# Schematic_proiect_v112.net
KiCad netlist of a schematic drawn in EAGLE
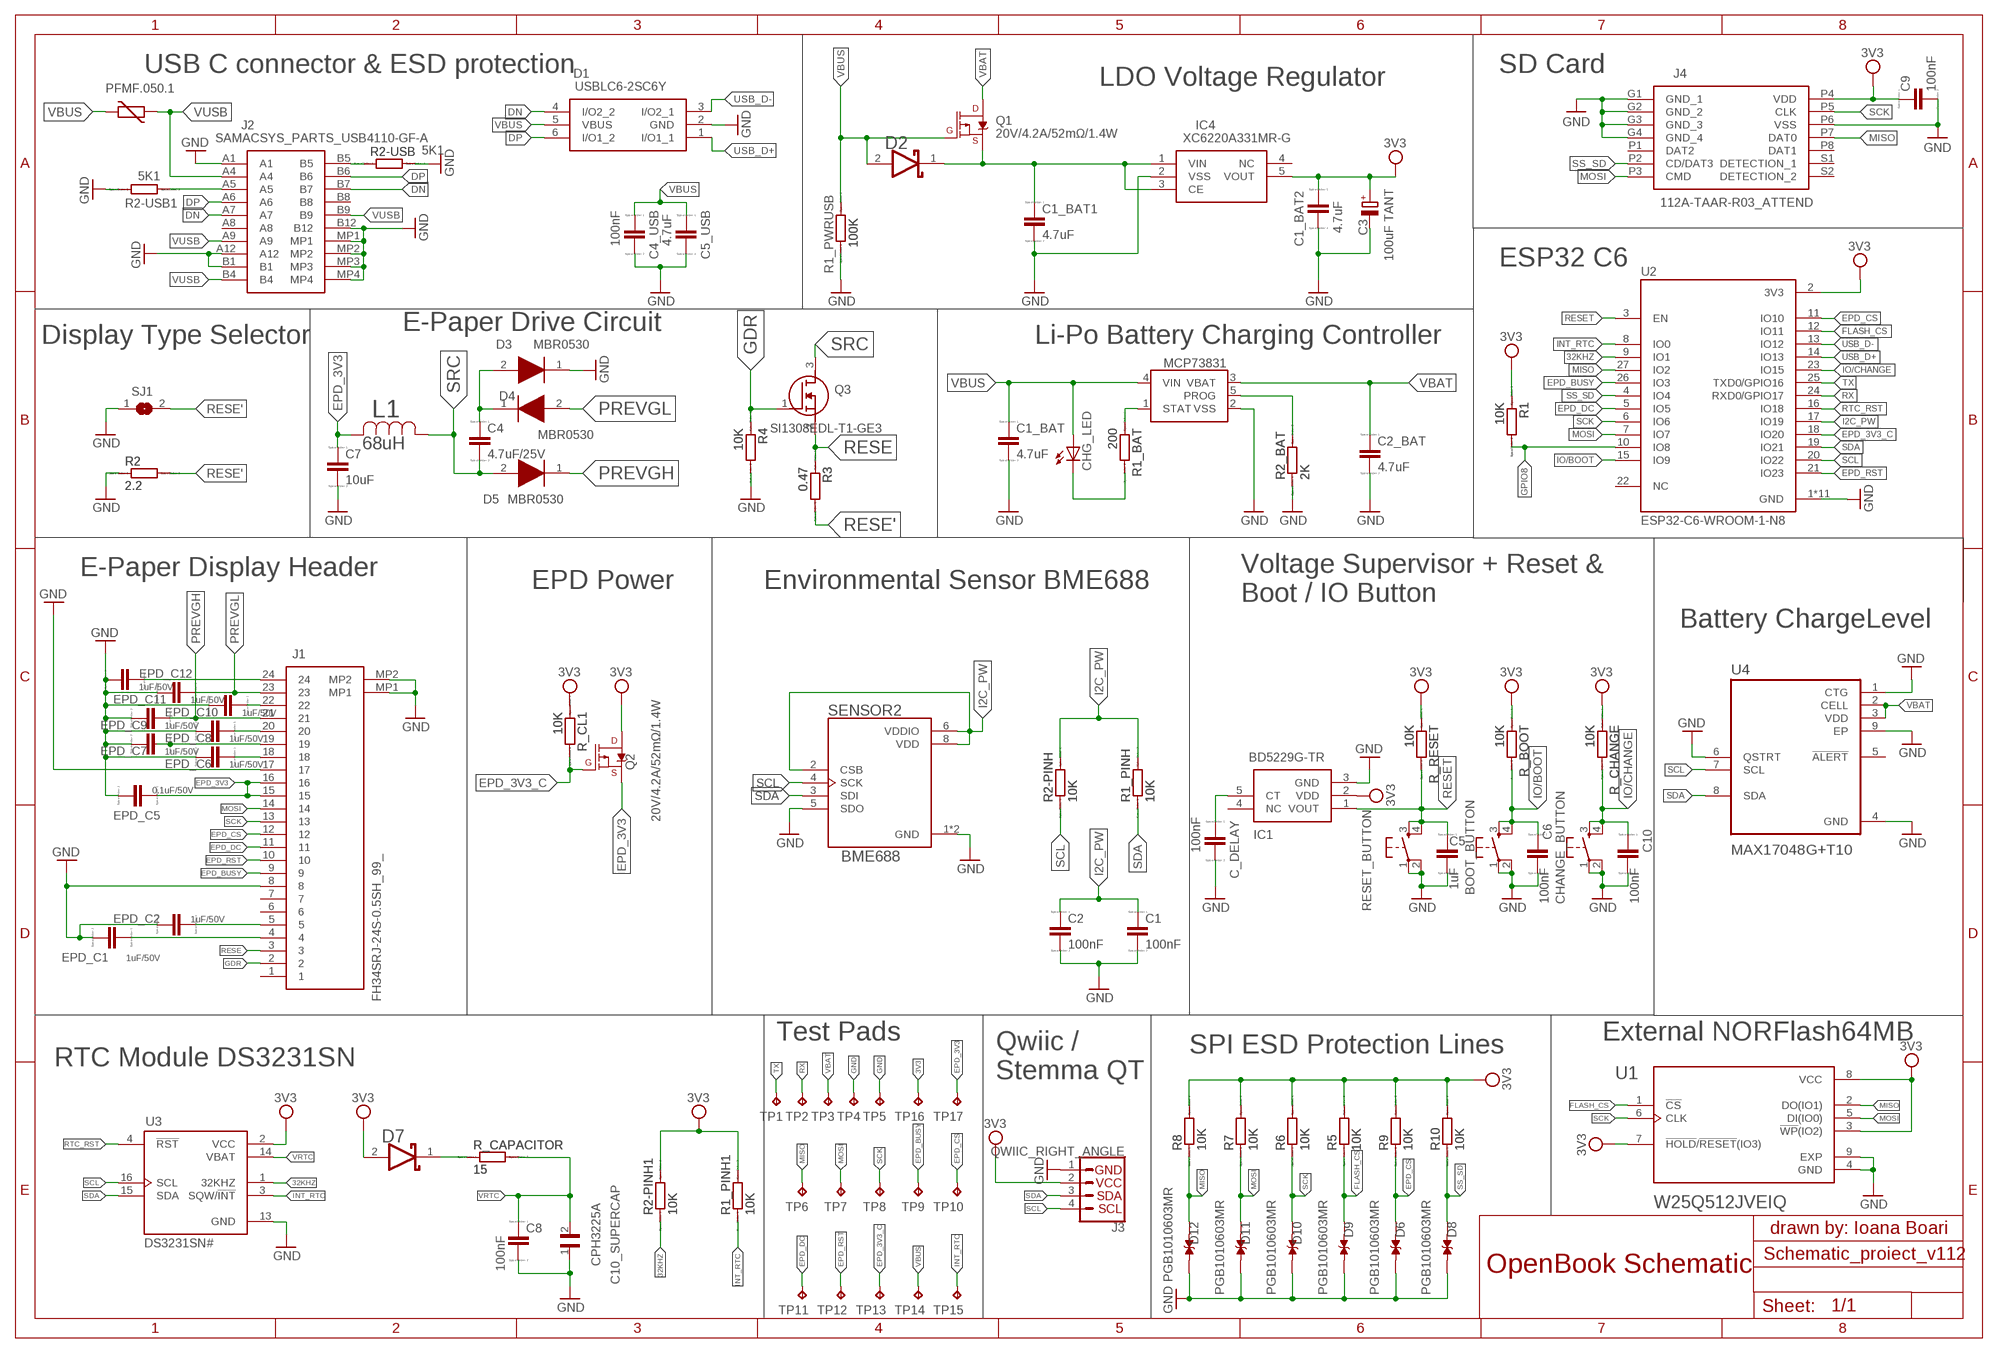
[diagram p0: schematic, sheet 1]

(export (version "E")
  (design (tool "Eeschema 10.0.6"))
  (components
    (comp (ref "BOOT_BUTTON")
      (value "BUTTON_CUSYOMV1")
      (footprint "eagle-import:MYBUTTON")
      (libsource (lib "eagle-import") (part "BUTTON_CUSYOMV1"))
    )
    (comp (ref "C1")
      (value "100nF")
      (footprint "eagle-import:ESP32_WROVER_EAGLE-LTSPICE_C0402")
      (libsource (lib "eagle-import") (part "ESP32_WROVER_EAGLE-LTSPICE_CC0402"))
    )
    (comp (ref "C1_BAT")
      (value "4.7uF")
      (footprint "eagle-import:ESP32_WROVER_EAGLE-LTSPICE_C0402")
      (libsource (lib "eagle-import") (part "ESP32_WROVER_EAGLE-LTSPICE_CC0402"))
    )
    (comp (ref "C1_BAT1")
      (value "4.7uF")
      (footprint "eagle-import:ESP32_WROVER_EAGLE-LTSPICE_C0402")
      (libsource (lib "eagle-import") (part "ESP32_WROVER_EAGLE-LTSPICE_CC0402"))
    )
    (comp (ref "C1_BAT2")
      (value "4.7uF")
      (footprint "eagle-import:EAGLE-LTSPICE_C0402")
      (libsource (lib "eagle-import") (part "EAGLE-LTSPICE_CC0402"))
    )
    (comp (ref "C2")
      (value "100nF")
      (footprint "eagle-import:ESP32_WROVER_EAGLE-LTSPICE_C0402")
      (libsource (lib "eagle-import") (part "ESP32_WROVER_EAGLE-LTSPICE_CC0402"))
    )
    (comp (ref "C2_BAT")
      (value "4.7uF")
      (footprint "eagle-import:ESP32_WROVER_EAGLE-LTSPICE_C0402")
      (libsource (lib "eagle-import") (part "ESP32_WROVER_EAGLE-LTSPICE_CC0402"))
    )
    (comp (ref "C3")
      (value "100uF TANT")
      (footprint "eagle-import:RCL_CT3528")
      (libsource (lib "eagle-import") (part "RCL_CPOL-EUCT3528"))
    )
    (comp (ref "C4")
      (value "4.7uF/25V")
      (footprint "eagle-import:ESP32_WROVER_EAGLE-LTSPICE_C0402")
      (libsource (lib "eagle-import") (part "ESP32_WROVER_EAGLE-LTSPICE_CC0402"))
    )
    (comp (ref "C4_USB")
      (value "100nF")
      (footprint "eagle-import:ESP32_WROVER_EAGLE-LTSPICE_C0402")
      (libsource (lib "eagle-import") (part "ESP32_WROVER_EAGLE-LTSPICE_CC0402"))
    )
    (comp (ref "C5")
      (value "1uF")
      (footprint "eagle-import:ESP32_WROVER_EAGLE-LTSPICE_C0402")
      (libsource (lib "eagle-import") (part "ESP32_WROVER_EAGLE-LTSPICE_CC0402"))
    )
    (comp (ref "C5_USB")
      (value "4.7uF")
      (footprint "eagle-import:ESP32_WROVER_EAGLE-LTSPICE_C0402")
      (libsource (lib "eagle-import") (part "ESP32_WROVER_EAGLE-LTSPICE_CC0402"))
    )
    (comp (ref "C6")
      (value "100nF")
      (footprint "eagle-import:ESP32_WROVER_EAGLE-LTSPICE_C0402")
      (libsource (lib "eagle-import") (part "ESP32_WROVER_EAGLE-LTSPICE_CC0402"))
    )
    (comp (ref "C7")
      (value "10uF")
      (footprint "eagle-import:ESP32_WROVER_EAGLE-LTSPICE_C0402")
      (libsource (lib "eagle-import") (part "ESP32_WROVER_EAGLE-LTSPICE_CC0402"))
    )
    (comp (ref "C8")
      (value "100nF")
      (footprint "eagle-import:ESP32_WROVER_EAGLE-LTSPICE_C0402")
      (libsource (lib "eagle-import") (part "ESP32_WROVER_EAGLE-LTSPICE_CC0402"))
    )
    (comp (ref "C9")
      (value "100nF")
      (footprint "eagle-import:ESP32_WROVER_EAGLE-LTSPICE_C0402")
      (libsource (lib "eagle-import") (part "ESP32_WROVER_EAGLE-LTSPICE_CC0402"))
    )
    (comp (ref "C10")
      (value "100nF")
      (footprint "eagle-import:ESP32_WROVER_EAGLE-LTSPICE_C0402")
      (libsource (lib "eagle-import") (part "ESP32_WROVER_EAGLE-LTSPICE_CC0402"))
    )
    (comp (ref "C10_SUPERCAP")
      (value "CPH3225A")
      (footprint "eagle-import:CAPCP3225X100N")
      (fields (field (name "MF") "Seiko Instruments"))
      (libsource (lib "eagle-import") (part "CPH3225A"))
    )
    (comp (ref "CHANGE_BUTTON")
      (value "BUTTON_CUSYOMV1")
      (footprint "eagle-import:MYBUTTON")
      (libsource (lib "eagle-import") (part "BUTTON_CUSYOMV1"))
    )
    (comp (ref "CHG_LED")
      (value "ADAFRUIT_LEDCHIP-LED0603")
      (footprint "eagle-import:ADAFRUIT_CHIP-LED0603")
      (libsource (lib "eagle-import") (part "ADAFRUIT_LEDCHIP-LED0603"))
    )
    (comp (ref "C_DELAY")
      (value "100nF")
      (footprint "eagle-import:ESP32_WROVER_EAGLE-LTSPICE_C0402")
      (libsource (lib "eagle-import") (part "ESP32_WROVER_EAGLE-LTSPICE_CC0402"))
    )
    (comp (ref "D1")
      (value "USBLC6-2SC6Y")
      (footprint "eagle-import:SOT95P280X145-6N")
      (fields (field (name "MF") "STMicroelectronics"))
      (libsource (lib "eagle-import") (part "USBLC6-2SC6Y"))
    )
    (comp (ref "D2")
      (value "ESP32_WROVER_AVX---SD0805S020S1R0_AVX_SD0805S020S1R0_0_0AVX_SD0805S020S1R0_0_0")
      (footprint "eagle-import:ESP32_WROVER_AVX---SD0805S020S1R0_AVX_SD0805S020S1R0_0")
      (fields
        (field (name "DIGIKEY_PART_NUMBER") "478-7800-1-ND")
        (field (name "MF") "AVX")
        (field (name "MOUSER_PART_NUMBER") "581-SD0805S020S1R0")
      )
      (libsource (lib "eagle-import") (part "ESP32_WROVER_AVX---SD0805S020S1R0_AVX_SD0805S020S1R0_0_0AVX_SD0805S020S1R0_0_0"))
    )
    (comp (ref "D3")
      (value "MBR0530")
      (footprint "eagle-import:SOD3716X135N")
      (fields (field (name "MF") "ON Semiconductor"))
      (libsource (lib "eagle-import") (part "MBR0530"))
    )
    (comp (ref "D4")
      (value "MBR0530")
      (footprint "eagle-import:SOD3716X135N")
      (fields (field (name "MF") "ON Semiconductor"))
      (libsource (lib "eagle-import") (part "MBR0530"))
    )
    (comp (ref "D5")
      (value "MBR0530")
      (footprint "eagle-import:SOD3716X135N")
      (fields (field (name "MF") "ON Semiconductor"))
      (libsource (lib "eagle-import") (part "MBR0530"))
    )
    (comp (ref "D6")
      (value "PGB1010603MR")
      (footprint "eagle-import:DIOC1608X36N")
      (fields (field (name "MF") "Littelfuse Inc."))
      (libsource (lib "eagle-import") (part "PGB1010603MR"))
    )
    (comp (ref "D7")
      (value "ESP32_WROVER_AVX---SD0805S020S1R0_AVX_SD0805S020S1R0_0_0AVX_SD0805S020S1R0_0_0")
      (footprint "eagle-import:ESP32_WROVER_AVX---SD0805S020S1R0_AVX_SD0805S020S1R0_0")
      (fields
        (field (name "DIGIKEY_PART_NUMBER") "478-7800-1-ND")
        (field (name "MF") "AVX")
        (field (name "MOUSER_PART_NUMBER") "581-SD0805S020S1R0")
      )
      (libsource (lib "eagle-import") (part "ESP32_WROVER_AVX---SD0805S020S1R0_AVX_SD0805S020S1R0_0_0AVX_SD0805S020S1R0_0_0"))
    )
    (comp (ref "D8")
      (value "PGB1010603MR")
      (footprint "eagle-import:DIOC1608X36N")
      (fields (field (name "MF") "Littelfuse Inc."))
      (libsource (lib "eagle-import") (part "PGB1010603MR"))
    )
    (comp (ref "D9")
      (value "PGB1010603MR")
      (footprint "eagle-import:DIOC1608X36N")
      (fields (field (name "MF") "Littelfuse Inc."))
      (libsource (lib "eagle-import") (part "PGB1010603MR"))
    )
    (comp (ref "D10")
      (value "PGB1010603MR")
      (footprint "eagle-import:DIOC1608X36N")
      (fields (field (name "MF") "Littelfuse Inc."))
      (libsource (lib "eagle-import") (part "PGB1010603MR"))
    )
    (comp (ref "D11")
      (value "PGB1010603MR")
      (footprint "eagle-import:DIOC1608X36N")
      (fields (field (name "MF") "Littelfuse Inc."))
      (libsource (lib "eagle-import") (part "PGB1010603MR"))
    )
    (comp (ref "D12")
      (value "PGB1010603MR")
      (footprint "eagle-import:DIOC1608X36N")
      (fields (field (name "MF") "Littelfuse Inc."))
      (libsource (lib "eagle-import") (part "PGB1010603MR"))
    )
    (comp (ref "EPD_C1")
      (value "1uF/50V")
      (footprint "eagle-import:ESP32_WROVER_EAGLE-LTSPICE_C0402")
      (libsource (lib "eagle-import") (part "ESP32_WROVER_EAGLE-LTSPICE_CC0402"))
    )
    (comp (ref "EPD_C2")
      (value "1uF/50V")
      (footprint "eagle-import:ESP32_WROVER_EAGLE-LTSPICE_C0402")
      (libsource (lib "eagle-import") (part "ESP32_WROVER_EAGLE-LTSPICE_CC0402"))
    )
    (comp (ref "EPD_C5")
      (value "0.1uF/50V")
      (footprint "eagle-import:ESP32_WROVER_EAGLE-LTSPICE_C0402")
      (libsource (lib "eagle-import") (part "ESP32_WROVER_EAGLE-LTSPICE_CC0402"))
    )
    (comp (ref "EPD_C6")
      (value "1uF/50V")
      (footprint "eagle-import:ESP32_WROVER_EAGLE-LTSPICE_C0402")
      (libsource (lib "eagle-import") (part "ESP32_WROVER_EAGLE-LTSPICE_CC0402"))
    )
    (comp (ref "EPD_C7")
      (value "1uF/50V")
      (footprint "eagle-import:ESP32_WROVER_EAGLE-LTSPICE_C0402")
      (libsource (lib "eagle-import") (part "ESP32_WROVER_EAGLE-LTSPICE_CC0402"))
    )
    (comp (ref "EPD_C8")
      (value "1uF/50V")
      (footprint "eagle-import:ESP32_WROVER_EAGLE-LTSPICE_C0402")
      (libsource (lib "eagle-import") (part "ESP32_WROVER_EAGLE-LTSPICE_CC0402"))
    )
    (comp (ref "EPD_C9")
      (value "1uF/50V")
      (footprint "eagle-import:ESP32_WROVER_EAGLE-LTSPICE_C0402")
      (libsource (lib "eagle-import") (part "ESP32_WROVER_EAGLE-LTSPICE_CC0402"))
    )
    (comp (ref "EPD_C10")
      (value "1uF/50V")
      (footprint "eagle-import:ESP32_WROVER_EAGLE-LTSPICE_C0402")
      (libsource (lib "eagle-import") (part "ESP32_WROVER_EAGLE-LTSPICE_CC0402"))
    )
    (comp (ref "EPD_C11")
      (value "1uF/50V")
      (footprint "eagle-import:ESP32_WROVER_EAGLE-LTSPICE_C0402")
      (libsource (lib "eagle-import") (part "ESP32_WROVER_EAGLE-LTSPICE_CC0402"))
    )
    (comp (ref "EPD_C12")
      (value "1uF/50V")
      (footprint "eagle-import:ESP32_WROVER_EAGLE-LTSPICE_C0402")
      (libsource (lib "eagle-import") (part "ESP32_WROVER_EAGLE-LTSPICE_CC0402"))
    )
    (comp (ref "IC1")
      (value "BD5229G-TR")
      (footprint "eagle-import:SOT95P280X125-5N")
      (fields (field (name "MOUSER_PART_NUMBER") "755-BD5229G-TR"))
      (libsource (lib "eagle-import") (part "BD5229G-TR"))
    )
    (comp (ref "IC4")
      (value "XC6220A331MR-G")
      (footprint "eagle-import:SOT95P280X120-5N")
      (fields (field (name "MOUSER_PART_NUMBER") "865-XC6220A331MR-G"))
      (libsource (lib "eagle-import") (part "XC6220A331MR-G"))
    )
    (comp (ref "J1")
      (value "FH34SRJ-24S-0.5SH_99_")
      (footprint "eagle-import:FH34SRJ24S05SH99")
      (fields
        (field (name "MANUFACTURER_PART_NUMBER") "FH34SRJ-24S-0.5SH(99)")
        (field (name "MOUSER_PART_NUMBER") "798-FH34SRJ24S05SH99")
      )
      (libsource (lib "eagle-import") (part "FH34SRJ-24S-0.5SH_99_"))
    )
    (comp (ref "J2")
      (value "SAMACSYS_PARTS_USB4110-GF-A")
      (footprint "eagle-import:SAMACSYS_PARTS_USB4110GFA")
      (fields
        (field (name "MANUFACTURER_PART_NUMBER") "USB4110-GF-A")
        (field (name "MOUSER_PART_NUMBER") "640-USB4110-GF-A")
      )
      (libsource (lib "eagle-import") (part "SAMACSYS_PARTS_USB4110-GF-A"))
    )
    (comp (ref "J3")
      (value "QWIIC_RIGHT_ANGLE")
      (footprint "eagle-import:JST04_1MM_RA")
      (libsource (lib "eagle-import") (part "QWIIC_CONNECTORJS-1MM"))
    )
    (comp (ref "J4")
      (value "112A-TAAR-R03_ATTEND")
      (footprint "eagle-import:112ATAARR03ATTEND")
      (fields (field (name "MANUFACTURER_PART_NUMBER") "112A-TAAR-R03 ATTEND"))
      (libsource (lib "eagle-import") (part "112A-TAAR-R03_ATTEND"))
    )
    (comp (ref "L1")
      (value "68uH")
      (footprint "eagle-import:IND_4828-WE-TPC_WRE")
      (fields
        (field (name "MANUFACTURER_PART_NUMBER") "744043680")
        (field (name "COPYRIGHT") "Copyright (C) 2024 Ultra Librarian. All rights reserved.")
      )
      (libsource (lib "eagle-import") (part "744043680IND_4828-WE-TPC_WRE"))
    )
    (comp (ref "MCP73831")
      (value "MCP73831")
      (footprint "eagle-import:ESP32_WROVER_SPARKFUN-IC-POWER_SOT23-5")
      (libsource (lib "eagle-import") (part "ESP32_WROVER_SPARKFUN-IC-POWER_MCP73831"))
    )
    (comp (ref "PFMF.050.1")
      (value "ESP32C6_VARISTORCN1812")
      (footprint "eagle-import:ESP32C6_VARISTOR_CT_CN1812")
      (libsource (lib "eagle-import") (part "ESP32C6_VARISTORCN1812"))
    )
    (comp (ref "Q1")
      (value "20V/4.2A/52mΩ/1.4W")
      (footprint "eagle-import:ESP32_WROVER_SPARKFUN-DISCRETESEMI_SOT23-3")
      (libsource (lib "eagle-import") (part "ESP32_WROVER_SPARKFUN-DISCRETESEMI_MOSFET_PCH-DMG2305UX-7"))
    )
    (comp (ref "Q2")
      (value "20V/4.2A/52mΩ/1.4W")
      (footprint "eagle-import:ESP32_WROVER_SPARKFUN-DISCRETESEMI_SOT23-3")
      (libsource (lib "eagle-import") (part "ESP32_WROVER_SPARKFUN-DISCRETESEMI_MOSFET_PCH-DMG2305UX-7"))
    )
    (comp (ref "Q3")
      (value "SI1308EDL-T1-GE3")
      (footprint "eagle-import:SOT65P210X110-3N")
      (fields (field (name "MF") "Vishay Siliconix"))
      (libsource (lib "eagle-import") (part "SI1308EDL-T1-GE3"))
    )
    (comp (ref "R1")
      (value "10K")
      (footprint "eagle-import:ESP32_WROVER_EAGLE-LTSPICE_R0402")
      (libsource (lib "eagle-import") (part "ESP32_WROVER_EAGLE-LTSPICE_RR0402"))
    )
    (comp (ref "R1_BAT")
      (value "200")
      (footprint "eagle-import:ESP32_WROVER_EAGLE-LTSPICE_R0402")
      (libsource (lib "eagle-import") (part "ESP32_WROVER_EAGLE-LTSPICE_RR0402"))
    )
    (comp (ref "R1_PINH")
      (value "10K")
      (footprint "eagle-import:ESP32_WROVER_EAGLE-LTSPICE_R0402")
      (libsource (lib "eagle-import") (part "ESP32_WROVER_EAGLE-LTSPICE_RR0402"))
    )
    (comp (ref "R1_PINH1")
      (value "10K")
      (footprint "eagle-import:ESP32_WROVER_EAGLE-LTSPICE_R0402")
      (libsource (lib "eagle-import") (part "ESP32_WROVER_EAGLE-LTSPICE_RR0402"))
    )
    (comp (ref "R1_PWRUSB")
      (value "100K")
      (footprint "eagle-import:ESP32_WROVER_EAGLE-LTSPICE_R0402")
      (libsource (lib "eagle-import") (part "ESP32_WROVER_EAGLE-LTSPICE_RR0402"))
    )
    (comp (ref "R2")
      (value "2.2")
      (footprint "eagle-import:ESP32_WROVER_EAGLE-LTSPICE_R0402")
      (libsource (lib "eagle-import") (part "ESP32_WROVER_EAGLE-LTSPICE_RR0402"))
    )
    (comp (ref "R2-PINH")
      (value "10K")
      (footprint "eagle-import:ESP32_WROVER_EAGLE-LTSPICE_R0402")
      (libsource (lib "eagle-import") (part "ESP32_WROVER_EAGLE-LTSPICE_RR0402"))
    )
    (comp (ref "R2-PINH1")
      (value "10K")
      (footprint "eagle-import:ESP32_WROVER_EAGLE-LTSPICE_R0402")
      (libsource (lib "eagle-import") (part "ESP32_WROVER_EAGLE-LTSPICE_RR0402"))
    )
    (comp (ref "R2-USB")
      (value "5K1")
      (footprint "eagle-import:ESP32_WROVER_EAGLE-LTSPICE_R0402")
      (libsource (lib "eagle-import") (part "ESP32_WROVER_EAGLE-LTSPICE_RR0402"))
    )
    (comp (ref "R2-USB1")
      (value "5K1")
      (footprint "eagle-import:ESP32_WROVER_EAGLE-LTSPICE_R0402")
      (libsource (lib "eagle-import") (part "ESP32_WROVER_EAGLE-LTSPICE_RR0402"))
    )
    (comp (ref "R2_BAT")
      (value "2K")
      (footprint "eagle-import:ESP32_WROVER_EAGLE-LTSPICE_R0402")
      (libsource (lib "eagle-import") (part "ESP32_WROVER_EAGLE-LTSPICE_RR0402"))
    )
    (comp (ref "R3")
      (value "0.47")
      (footprint "eagle-import:ESP32_WROVER_EAGLE-LTSPICE_R0402")
      (libsource (lib "eagle-import") (part "ESP32_WROVER_EAGLE-LTSPICE_RR0402"))
    )
    (comp (ref "R4")
      (value "10K")
      (footprint "eagle-import:ESP32_WROVER_EAGLE-LTSPICE_R0402")
      (libsource (lib "eagle-import") (part "ESP32_WROVER_EAGLE-LTSPICE_RR0402"))
    )
    (comp (ref "R5")
      (value "10K")
      (footprint "eagle-import:ESP32_WROVER_EAGLE-LTSPICE_R0402")
      (libsource (lib "eagle-import") (part "ESP32_WROVER_EAGLE-LTSPICE_RR0402"))
    )
    (comp (ref "R6")
      (value "10K")
      (footprint "eagle-import:ESP32_WROVER_EAGLE-LTSPICE_R0402")
      (libsource (lib "eagle-import") (part "ESP32_WROVER_EAGLE-LTSPICE_RR0402"))
    )
    (comp (ref "R7")
      (value "10K")
      (footprint "eagle-import:ESP32_WROVER_EAGLE-LTSPICE_R0402")
      (libsource (lib "eagle-import") (part "ESP32_WROVER_EAGLE-LTSPICE_RR0402"))
    )
    (comp (ref "R8")
      (value "10K")
      (footprint "eagle-import:ESP32_WROVER_EAGLE-LTSPICE_R0402")
      (libsource (lib "eagle-import") (part "ESP32_WROVER_EAGLE-LTSPICE_RR0402"))
    )
    (comp (ref "R9")
      (value "10K")
      (footprint "eagle-import:ESP32_WROVER_EAGLE-LTSPICE_R0402")
      (libsource (lib "eagle-import") (part "ESP32_WROVER_EAGLE-LTSPICE_RR0402"))
    )
    (comp (ref "R10")
      (value "10K")
      (footprint "eagle-import:ESP32_WROVER_EAGLE-LTSPICE_R0402")
      (libsource (lib "eagle-import") (part "ESP32_WROVER_EAGLE-LTSPICE_RR0402"))
    )
    (comp (ref "RESET_BUTTON")
      (value "BUTTON_CUSYOMV1")
      (footprint "eagle-import:MYBUTTON")
      (libsource (lib "eagle-import") (part "BUTTON_CUSYOMV1"))
    )
    (comp (ref "R_BOOT")
      (value "10K")
      (footprint "eagle-import:ESP32_WROVER_EAGLE-LTSPICE_R0402")
      (libsource (lib "eagle-import") (part "ESP32_WROVER_EAGLE-LTSPICE_RR0402"))
    )
    (comp (ref "R_CAPACITOR")
      (value "15")
      (footprint "eagle-import:ESP32_WROVER_EAGLE-LTSPICE_R0402")
      (libsource (lib "eagle-import") (part "ESP32_WROVER_EAGLE-LTSPICE_RR0402"))
    )
    (comp (ref "R_CHANGE")
      (value "10K")
      (footprint "eagle-import:ESP32_WROVER_EAGLE-LTSPICE_R0402")
      (libsource (lib "eagle-import") (part "ESP32_WROVER_EAGLE-LTSPICE_RR0402"))
    )
    (comp (ref "R_CL1")
      (value "10K")
      (footprint "eagle-import:ESP32_WROVER_EAGLE-LTSPICE_R0402")
      (libsource (lib "eagle-import") (part "ESP32_WROVER_EAGLE-LTSPICE_RR0402"))
    )
    (comp (ref "R_RESET")
      (value "10K")
      (footprint "eagle-import:ESP32_WROVER_EAGLE-LTSPICE_R0402")
      (libsource (lib "eagle-import") (part "ESP32_WROVER_EAGLE-LTSPICE_RR0402"))
    )
    (comp (ref "SENSOR2")
      (value "BME688")
      (footprint "eagle-import:ESP32_WROVER_BME680_PSON80P300X300X100-8N")
      (fields (field (name "MF") "Bosch Sensortec") (field (name "MP") "BME680"))
      (libsource (lib "eagle-import") (part "ESP32_WROVER_BME680_BME680"))
    )
    (comp (ref "SJ1") (value "SJ") (footprint "eagle-import:SJ") (libsource (lib "eagle-import") (part "SJ")))
    (comp (ref "TP1")
      (value "TPTP20R")
      (footprint "eagle-import:TP20R")
      (libsource (lib "eagle-import") (part "TPTP20R"))
    )
    (comp (ref "TP2")
      (value "TPTP20R")
      (footprint "eagle-import:TP20R")
      (libsource (lib "eagle-import") (part "TPTP20R"))
    )
    (comp (ref "TP3")
      (value "TPTP20R")
      (footprint "eagle-import:TP20R")
      (libsource (lib "eagle-import") (part "TPTP20R"))
    )
    (comp (ref "TP4")
      (value "TPTP20R")
      (footprint "eagle-import:TP20R")
      (libsource (lib "eagle-import") (part "TPTP20R"))
    )
    (comp (ref "TP5")
      (value "TPTP20R")
      (footprint "eagle-import:TP20R")
      (libsource (lib "eagle-import") (part "TPTP20R"))
    )
    (comp (ref "TP6")
      (value "TPTP20R")
      (footprint "eagle-import:TP20R")
      (libsource (lib "eagle-import") (part "TPTP20R"))
    )
    (comp (ref "TP7")
      (value "TPTP20R")
      (footprint "eagle-import:TP20R")
      (libsource (lib "eagle-import") (part "TPTP20R"))
    )
    (comp (ref "TP8")
      (value "TPTP20R")
      (footprint "eagle-import:TP20R")
      (libsource (lib "eagle-import") (part "TPTP20R"))
    )
    (comp (ref "TP9")
      (value "TPTP20R")
      (footprint "eagle-import:TP20R")
      (libsource (lib "eagle-import") (part "TPTP20R"))
    )
    (comp (ref "TP10")
      (value "TPTP20R")
      (footprint "eagle-import:TP20R")
      (libsource (lib "eagle-import") (part "TPTP20R"))
    )
    (comp (ref "TP11")
      (value "TPTP20R")
      (footprint "eagle-import:TP20R")
      (libsource (lib "eagle-import") (part "TPTP20R"))
    )
    (comp (ref "TP12")
      (value "TPTP20R")
      (footprint "eagle-import:TP20R")
      (libsource (lib "eagle-import") (part "TPTP20R"))
    )
    (comp (ref "TP13")
      (value "TPTP20R")
      (footprint "eagle-import:TP20R")
      (libsource (lib "eagle-import") (part "TPTP20R"))
    )
    (comp (ref "TP14")
      (value "TPTP20R")
      (footprint "eagle-import:TP20R")
      (libsource (lib "eagle-import") (part "TPTP20R"))
    )
    (comp (ref "TP15")
      (value "TPTP20R")
      (footprint "eagle-import:TP20R")
      (libsource (lib "eagle-import") (part "TPTP20R"))
    )
    (comp (ref "TP16")
      (value "TPTP20R")
      (footprint "eagle-import:TP20R")
      (libsource (lib "eagle-import") (part "TPTP20R"))
    )
    (comp (ref "TP17")
      (value "TPTP20R")
      (footprint "eagle-import:TP20R")
      (libsource (lib "eagle-import") (part "TPTP20R"))
    )
    (comp (ref "U1")
      (value "W25Q512JVEIQ")
      (footprint "eagle-import:SON127P600X800X80-9N")
      (fields (field (name "MF") "Winbond Electronics"))
      (libsource (lib "eagle-import") (part "W25Q512JVEIQ"))
    )
    (comp (ref "U2")
      (value "ESP32-C6-WROOM-1-N8")
      (footprint "eagle-import:XCVR_ESP32-C6-WROOM-1-N8")
      (fields (field (name "MF") "Espressif Systems"))
      (libsource (lib "eagle-import") (part "ESP32-C6-WROOM-1-N8"))
    )
    (comp (ref "U3")
      (value "DS3231SN#")
      (footprint "eagle-import:SOIC127P1032X265-16N")
      (fields (field (name "MF") "Analog Devices"))
      (libsource (lib "eagle-import") (part "DS3231SN#"))
    )
    (comp (ref "U4")
      (value "MAX17048G+T10")
      (footprint "eagle-import:SON50P200X200X80-9N")
      (fields (field (name "MF") "Analog Devices"))
      (libsource (lib "eagle-import") (part "MAX17048G+T10"))
    )
  )
  (nets
    (net (code "1") (name "3V3") (class "Default")
      (node (ref "C1_BAT2") (pin "1") (pinfunction "1_1") (pintype "passive"))
      (node (ref "C3") (pin "+") (pinfunction "+_+") (pintype "passive"))
      (node (ref "C9") (pin "1") (pinfunction "1_1") (pintype "passive"))
      (node (ref "D7") (pin "2") (pinfunction "ANODE_2") (pintype "bidirectional"))
      (node (ref "IC1") (pin "2") (pinfunction "VDD_2") (pintype "bidirectional"))
      (node (ref "IC4") (pin "5") (pinfunction "VOUT_5") (pintype "bidirectional"))
      (node (ref "J3") (pin "2") (pinfunction "2_2") (pintype "power_in"))
      (node (ref "J4") (pin "P4") (pinfunction "VDD_P4") (pintype "bidirectional"))
      (node (ref "Q2") (pin "3") (pinfunction "D_3") (pintype "bidirectional"))
      (node (ref "R1") (pin "1") (pinfunction "1_1") (pintype "passive"))
      (node (ref "R10") (pin "2") (pinfunction "2_2") (pintype "passive"))
      (node (ref "R1_PINH1") (pin "2") (pinfunction "2_2") (pintype "passive"))
      (node (ref "R2-PINH1") (pin "2") (pinfunction "2_2") (pintype "passive"))
      (node (ref "R5") (pin "2") (pinfunction "2_2") (pintype "passive"))
      (node (ref "R6") (pin "2") (pinfunction "2_2") (pintype "passive"))
      (node (ref "R7") (pin "2") (pinfunction "2_2") (pintype "passive"))
      (node (ref "R8") (pin "2") (pinfunction "2_2") (pintype "passive"))
      (node (ref "R9") (pin "2") (pinfunction "2_2") (pintype "passive"))
      (node (ref "R_BOOT") (pin "1") (pinfunction "1_1") (pintype "passive"))
      (node (ref "R_CHANGE") (pin "1") (pinfunction "1_1") (pintype "passive"))
      (node (ref "R_CL1") (pin "1") (pinfunction "1_1") (pintype "passive"))
      (node (ref "R_RESET") (pin "1") (pinfunction "1_1") (pintype "passive"))
      (node (ref "TP16") (pin "TP") (pinfunction "TP_TP") (pintype "input"))
      (node (ref "U1") (pin "3") (pinfunction "~{WP}(IO2)_3") (pintype "bidirectional"))
      (node (ref "U1") (pin "7") (pinfunction "~{HOLD}/~{RESET}(IO3)_7") (pintype "bidirectional"))
      (node (ref "U1") (pin "8") (pinfunction "VCC_8") (pintype "power_in"))
      (node (ref "U2") (pin "2") (pinfunction "3V3_2") (pintype "power_in"))
      (node (ref "U3") (pin "2") (pinfunction "VCC_2") (pintype "power_in"))
    )
    (net (code "2") (name "32KHZ") (class "Default")
      (node (ref "R2-PINH1") (pin "1") (pinfunction "1_1") (pintype "passive"))
      (node (ref "U2") (pin "9") (pinfunction "IO1_9") (pintype "bidirectional"))
      (node (ref "U3") (pin "1") (pinfunction "32KHZ_1") (pintype "output"))
    )
    (net (code "3") (name "DN") (class "Default")
      (node (ref "D1") (pin "4") (pinfunction "I/O2_2_4") (pintype "bidirectional"))
      (node (ref "J2") (pin "A7") (pinfunction "A7_A7") (pintype "bidirectional"))
      (node (ref "J2") (pin "B7") (pinfunction "B7_B7") (pintype "bidirectional"))
    )
    (net (code "4") (name "DP") (class "Default")
      (node (ref "D1") (pin "6") (pinfunction "I/O1_2_6") (pintype "bidirectional"))
      (node (ref "J2") (pin "A6") (pinfunction "A6_A6") (pintype "bidirectional"))
      (node (ref "J2") (pin "B6") (pinfunction "B6_B6") (pintype "bidirectional"))
    )
    (net (code "5") (name "EPD_3V3") (class "Default")
      (node (ref "C7") (pin "1") (pinfunction "1_1") (pintype "passive"))
      (node (ref "EPD_C5") (pin "1") (pinfunction "1_1") (pintype "passive"))
      (node (ref "J1") (pin "15") (pinfunction "15_15") (pintype "bidirectional"))
      (node (ref "J1") (pin "16") (pinfunction "16_16") (pintype "bidirectional"))
      (node (ref "L1") (pin "2") (pinfunction "2_2") (pintype "passive"))
      (node (ref "Q2") (pin "2") (pinfunction "S_2") (pintype "bidirectional"))
      (node (ref "TP17") (pin "TP") (pinfunction "TP_TP") (pintype "input"))
    )
    (net (code "6") (name "EPD_3V3_C") (class "Default")
      (node (ref "Q2") (pin "1") (pinfunction "G_1") (pintype "bidirectional"))
      (node (ref "R_CL1") (pin "2") (pinfunction "2_2") (pintype "passive"))
      (node (ref "TP13") (pin "TP") (pinfunction "TP_TP") (pintype "input"))
      (node (ref "U2") (pin "18") (pinfunction "IO20_18") (pintype "bidirectional"))
    )
    (net (code "7") (name "EPD_BUSY") (class "Default")
      (node (ref "J1") (pin "9") (pinfunction "9_9") (pintype "bidirectional"))
      (node (ref "TP9") (pin "TP") (pinfunction "TP_TP") (pintype "input"))
      (node (ref "U2") (pin "26") (pinfunction "IO3_26") (pintype "bidirectional"))
    )
    (net (code "8") (name "EPD_CS") (class "Default")
      (node (ref "D6") (pin "1") (pinfunction "1_1") (pintype "passive"))
      (node (ref "J1") (pin "12") (pinfunction "12_12") (pintype "bidirectional"))
      (node (ref "R9") (pin "1") (pinfunction "1_1") (pintype "passive"))
      (node (ref "TP10") (pin "TP") (pinfunction "TP_TP") (pintype "input"))
      (node (ref "U2") (pin "11") (pinfunction "IO10_11") (pintype "bidirectional"))
    )
    (net (code "9") (name "EPD_DC") (class "Default")
      (node (ref "J1") (pin "11") (pinfunction "11_11") (pintype "bidirectional"))
      (node (ref "TP11") (pin "TP") (pinfunction "TP_TP") (pintype "input"))
      (node (ref "U2") (pin "5") (pinfunction "IO5_5") (pintype "bidirectional"))
    )
    (net (code "10") (name "EPD_RST") (class "Default")
      (node (ref "J1") (pin "10") (pinfunction "10_10") (pintype "bidirectional"))
      (node (ref "TP12") (pin "TP") (pinfunction "TP_TP") (pintype "input"))
      (node (ref "U2") (pin "21") (pinfunction "IO23_21") (pintype "bidirectional"))
    )
    (net (code "11") (name "FLASH_CS") (class "Default")
      (node (ref "D9") (pin "1") (pinfunction "1_1") (pintype "passive"))
      (node (ref "R5") (pin "1") (pinfunction "1_1") (pintype "passive"))
      (node (ref "U1") (pin "1") (pinfunction "~{CS}_1") (pintype "input"))
      (node (ref "U2") (pin "12") (pinfunction "IO11_12") (pintype "bidirectional"))
    )
    (net (code "12") (name "GDR") (class "Default")
      (node (ref "J1") (pin "2") (pinfunction "2_2") (pintype "bidirectional"))
      (node (ref "Q3") (pin "1") (pinfunction "G_1") (pintype "bidirectional"))
      (node (ref "R4") (pin "1") (pinfunction "1_1") (pintype "passive"))
    )
    (net (code "13") (name "GND") (class "Default")
      (node (ref "BOOT_BUTTON") (pin "1") (pinfunction "1_1") (pintype "passive"))
      (node (ref "BOOT_BUTTON") (pin "2") (pinfunction "2_2") (pintype "passive"))
      (node (ref "C1") (pin "2") (pinfunction "2_2") (pintype "passive"))
      (node (ref "C10") (pin "2") (pinfunction "2_2") (pintype "passive"))
      (node (ref "C10_SUPERCAP") (pin "1") (pinfunction "1_1") (pintype "passive"))
      (node (ref "C1_BAT") (pin "2") (pinfunction "2_2") (pintype "passive"))
      (node (ref "C1_BAT1") (pin "2") (pinfunction "2_2") (pintype "passive"))
      (node (ref "C1_BAT2") (pin "2") (pinfunction "2_2") (pintype "passive"))
      (node (ref "C2") (pin "2") (pinfunction "2_2") (pintype "passive"))
      (node (ref "C2_BAT") (pin "2") (pinfunction "2_2") (pintype "passive"))
      (node (ref "C3") (pin "-") (pinfunction "-_-") (pintype "passive"))
      (node (ref "C4_USB") (pin "2") (pinfunction "2_2") (pintype "passive"))
      (node (ref "C5") (pin "2") (pinfunction "2_2") (pintype "passive"))
      (node (ref "C5_USB") (pin "2") (pinfunction "2_2") (pintype "passive"))
      (node (ref "C6") (pin "2") (pinfunction "2_2") (pintype "passive"))
      (node (ref "C7") (pin "2") (pinfunction "2_2") (pintype "passive"))
      (node (ref "C8") (pin "2") (pinfunction "2_2") (pintype "passive"))
      (node (ref "C9") (pin "2") (pinfunction "2_2") (pintype "passive"))
      (node (ref "CHANGE_BUTTON") (pin "1") (pinfunction "1_1") (pintype "passive"))
      (node (ref "CHANGE_BUTTON") (pin "2") (pinfunction "2_2") (pintype "passive"))
      (node (ref "C_DELAY") (pin "2") (pinfunction "2_2") (pintype "passive"))
      (node (ref "D1") (pin "2") (pinfunction "GND_2") (pintype "bidirectional"))
      (node (ref "D10") (pin "2") (pinfunction "2_2") (pintype "passive"))
      (node (ref "D11") (pin "2") (pinfunction "2_2") (pintype "passive"))
      (node (ref "D12") (pin "2") (pinfunction "2_2") (pintype "passive"))
      (node (ref "D3") (pin "1") (pinfunction "K_1") (pintype "bidirectional"))
      (node (ref "D6") (pin "2") (pinfunction "2_2") (pintype "passive"))
      (node (ref "D8") (pin "2") (pinfunction "2_2") (pintype "passive"))
      (node (ref "D9") (pin "2") (pinfunction "2_2") (pintype "passive"))
      (node (ref "EPD_C1") (pin "2") (pinfunction "2_2") (pintype "passive"))
      (node (ref "EPD_C10") (pin "2") (pinfunction "2_2") (pintype "passive"))
      (node (ref "EPD_C11") (pin "2") (pinfunction "2_2") (pintype "passive"))
      (node (ref "EPD_C12") (pin "2") (pinfunction "2_2") (pintype "passive"))
      (node (ref "EPD_C2") (pin "2") (pinfunction "2_2") (pintype "passive"))
      (node (ref "EPD_C5") (pin "2") (pinfunction "2_2") (pintype "passive"))
      (node (ref "EPD_C6") (pin "2") (pinfunction "2_2") (pintype "passive"))
      (node (ref "EPD_C7") (pin "2") (pinfunction "2_2") (pintype "passive"))
      (node (ref "EPD_C8") (pin "2") (pinfunction "2_2") (pintype "passive"))
      (node (ref "EPD_C9") (pin "2") (pinfunction "2_2") (pintype "passive"))
      (node (ref "IC1") (pin "3") (pinfunction "GND_3") (pintype "bidirectional"))
      (node (ref "IC4") (pin "2") (pinfunction "VSS_2") (pintype "bidirectional"))
      (node (ref "J1") (pin "17") (pinfunction "17_17") (pintype "bidirectional"))
      (node (ref "J1") (pin "8") (pinfunction "8_8") (pintype "bidirectional"))
      (node (ref "J1") (pin "MP1") (pinfunction "MP1_MP1") (pintype "bidirectional"))
      (node (ref "J1") (pin "MP2") (pinfunction "MP2_MP2") (pintype "bidirectional"))
      (node (ref "J2") (pin "A1") (pinfunction "A1_A1") (pintype "bidirectional"))
      (node (ref "J2") (pin "A12") (pinfunction "A12_A12") (pintype "bidirectional"))
      (node (ref "J2") (pin "B1") (pinfunction "B1_B1") (pintype "bidirectional"))
      (node (ref "J2") (pin "B12") (pinfunction "B12_B12") (pintype "bidirectional"))
      (node (ref "J2") (pin "MP1") (pinfunction "MP1_MP1") (pintype "bidirectional"))
      (node (ref "J2") (pin "MP2") (pinfunction "MP2_MP2") (pintype "bidirectional"))
      (node (ref "J2") (pin "MP3") (pinfunction "MP3_MP3") (pintype "bidirectional"))
      (node (ref "J2") (pin "MP4") (pinfunction "MP4_MP4") (pintype "bidirectional"))
      (node (ref "J3") (pin "1") (pinfunction "1_1") (pintype "power_in"))
      (node (ref "J4") (pin "G1") (pinfunction "GND_1_G1") (pintype "bidirectional"))
      (node (ref "J4") (pin "G2") (pinfunction "GND_2_G2") (pintype "bidirectional"))
      (node (ref "J4") (pin "G3") (pinfunction "GND_3_G3") (pintype "bidirectional"))
      (node (ref "J4") (pin "G4") (pinfunction "GND_4_G4") (pintype "bidirectional"))
      (node (ref "J4") (pin "P6") (pinfunction "VSS_P6") (pintype "bidirectional"))
      (node (ref "MCP73831") (pin "2") (pinfunction "VSS_2") (pintype "power_in"))
      (node (ref "R1_PWRUSB") (pin "1") (pinfunction "1_1") (pintype "passive"))
      (node (ref "R2") (pin "1") (pinfunction "1_1") (pintype "passive"))
      (node (ref "R2-USB") (pin "2") (pinfunction "2_2") (pintype "passive"))
      (node (ref "R2-USB1") (pin "1") (pinfunction "1_1") (pintype "passive"))
      (node (ref "R2_BAT") (pin "1") (pinfunction "1_1") (pintype "passive"))
      (node (ref "R4") (pin "2") (pinfunction "2_2") (pintype "passive"))
      (node (ref "RESET_BUTTON") (pin "1") (pinfunction "1_1") (pintype "passive"))
      (node (ref "RESET_BUTTON") (pin "2") (pinfunction "2_2") (pintype "passive"))
      (node (ref "SENSOR2") (pin "1") (pinfunction "GND_1") (pintype "power_in"))
      (node (ref "SENSOR2") (pin "5") (pinfunction "SDO_5") (pintype "bidirectional"))
      (node (ref "SENSOR2") (pin "7") (pinfunction "GND_7") (pintype "power_in"))
      (node (ref "SJ1") (pin "1") (pinfunction "1_1") (pintype "passive"))
      (node (ref "TP4") (pin "TP") (pinfunction "TP_TP") (pintype "input"))
      (node (ref "TP5") (pin "TP") (pinfunction "TP_TP") (pintype "input"))
      (node (ref "U1") (pin "4") (pinfunction "GND_4") (pintype "power_in"))
      (node (ref "U1") (pin "9") (pinfunction "EXP_9") (pintype "passive"))
      (node (ref "U2") (pin "1") (pinfunction "GND_1") (pintype "power_in"))
      (node (ref "U2") (pin "28") (pinfunction "GND_28") (pintype "power_in"))
      (node (ref "U2") (pin "29_1") (pinfunction "GND_29_1") (pintype "power_in"))
      (node (ref "U2") (pin "29_2") (pinfunction "GND_29_2") (pintype "power_in"))
      (node (ref "U2") (pin "29_3") (pinfunction "GND_29_3") (pintype "power_in"))
      (node (ref "U2") (pin "29_4") (pinfunction "GND_29_4") (pintype "power_in"))
      (node (ref "U2") (pin "29_5") (pinfunction "GND_29_5") (pintype "power_in"))
      (node (ref "U2") (pin "29_6") (pinfunction "GND_29_6") (pintype "power_in"))
      (node (ref "U2") (pin "29_7") (pinfunction "GND_29_7") (pintype "power_in"))
      (node (ref "U2") (pin "29_8") (pinfunction "GND_29_8") (pintype "power_in"))
      (node (ref "U2") (pin "29_9") (pinfunction "GND_29_9") (pintype "power_in"))
      (node (ref "U3") (pin "13") (pinfunction "GND_13") (pintype "power_in"))
      (node (ref "U4") (pin "1") (pinfunction "CTG_1") (pintype "power_in"))
      (node (ref "U4") (pin "4") (pinfunction "GND_4") (pintype "power_in"))
      (node (ref "U4") (pin "6") (pinfunction "QSTRT_6") (pintype "input"))
      (node (ref "U4") (pin "9") (pinfunction "EP_9") (pintype "power_in"))
    )
    (net (code "14") (name "GPIO8") (class "Default")
      (node (ref "R1") (pin "2") (pinfunction "2_2") (pintype "passive"))
      (node (ref "U2") (pin "10") (pinfunction "IO8_10") (pintype "bidirectional"))
    )
    (net (code "15") (name "I2C_PW") (class "Default")
      (node (ref "C1") (pin "1") (pinfunction "1_1") (pintype "passive"))
      (node (ref "C2") (pin "1") (pinfunction "1_1") (pintype "passive"))
      (node (ref "R1_PINH") (pin "2") (pinfunction "2_2") (pintype "passive"))
      (node (ref "R2-PINH") (pin "2") (pinfunction "2_2") (pintype "passive"))
      (node (ref "SENSOR2") (pin "2") (pinfunction "CSB_2") (pintype "input"))
      (node (ref "SENSOR2") (pin "6") (pinfunction "VDDIO_6") (pintype "power_in"))
      (node (ref "SENSOR2") (pin "8") (pinfunction "VDD_8") (pintype "power_in"))
      (node (ref "U2") (pin "17") (pinfunction "IO19_17") (pintype "bidirectional"))
    )
    (net (code "16") (name "INT_RTC") (class "Default")
      (node (ref "R1_PINH1") (pin "1") (pinfunction "1_1") (pintype "passive"))
      (node (ref "TP15") (pin "TP") (pinfunction "TP_TP") (pintype "input"))
      (node (ref "U2") (pin "8") (pinfunction "IO0_8") (pintype "bidirectional"))
      (node (ref "U3") (pin "3") (pinfunction "SQW/~{INT}_3") (pintype "output"))
    )
    (net (code "17") (name "IO{slash}BOOT") (class "Default")
      (node (ref "BOOT_BUTTON") (pin "3") (pinfunction "3_3") (pintype "passive"))
      (node (ref "BOOT_BUTTON") (pin "4") (pinfunction "4_4") (pintype "passive"))
      (node (ref "C6") (pin "1") (pinfunction "1_1") (pintype "passive"))
      (node (ref "R_BOOT") (pin "2") (pinfunction "2_2") (pintype "passive"))
      (node (ref "U2") (pin "15") (pinfunction "IO9_15") (pintype "bidirectional"))
    )
    (net (code "18") (name "IO{slash}CHANGE") (class "Default")
      (node (ref "C10") (pin "1") (pinfunction "1_1") (pintype "passive"))
      (node (ref "CHANGE_BUTTON") (pin "3") (pinfunction "3_3") (pintype "passive"))
      (node (ref "CHANGE_BUTTON") (pin "4") (pinfunction "4_4") (pintype "passive"))
      (node (ref "R_CHANGE") (pin "2") (pinfunction "2_2") (pintype "passive"))
      (node (ref "U2") (pin "23") (pinfunction "IO15_23") (pintype "bidirectional"))
    )
    (net (code "19") (name "MISO") (class "Default")
      (node (ref "D12") (pin "1") (pinfunction "1_1") (pintype "passive"))
      (node (ref "J4") (pin "P7") (pinfunction "DAT0_P7") (pintype "bidirectional"))
      (node (ref "R8") (pin "1") (pinfunction "1_1") (pintype "passive"))
      (node (ref "TP6") (pin "TP") (pinfunction "TP_TP") (pintype "input"))
      (node (ref "U1") (pin "2") (pinfunction "DO(IO1)_2") (pintype "bidirectional"))
      (node (ref "U2") (pin "27") (pinfunction "IO2_27") (pintype "bidirectional"))
    )
    (net (code "20") (name "MOSI") (class "Default")
      (node (ref "D11") (pin "1") (pinfunction "1_1") (pintype "passive"))
      (node (ref "J1") (pin "14") (pinfunction "14_14") (pintype "bidirectional"))
      (node (ref "J4") (pin "P3") (pinfunction "CMD_P3") (pintype "bidirectional"))
      (node (ref "R7") (pin "1") (pinfunction "1_1") (pintype "passive"))
      (node (ref "TP7") (pin "TP") (pinfunction "TP_TP") (pintype "input"))
      (node (ref "U1") (pin "5") (pinfunction "DI(IO0)_5") (pintype "bidirectional"))
      (node (ref "U2") (pin "7") (pinfunction "IO7_7") (pintype "bidirectional"))
    )
    (net (code "21") (name "Net-(CHG_LED-PadC)") (class "Default")
      (node (ref "CHG_LED") (pin "C") (pinfunction "C_C") (pintype "passive"))
      (node (ref "R1_BAT") (pin "2") (pinfunction "2_2") (pintype "passive"))
    )
    (net (code "22") (name "Net-(D2-CATHODE)") (class "Default")
      (node (ref "C1_BAT1") (pin "1") (pinfunction "1_1") (pintype "passive"))
      (node (ref "D2") (pin "1") (pinfunction "CATHODE_1") (pintype "bidirectional"))
      (node (ref "IC4") (pin "1") (pinfunction "VIN_1") (pintype "bidirectional"))
      (node (ref "IC4") (pin "3") (pinfunction "CE_3") (pintype "bidirectional"))
      (node (ref "Q1") (pin "2") (pinfunction "S_2") (pintype "bidirectional"))
    )
    (net (code "23") (name "Net-(D3-A)") (class "Default")
      (node (ref "C4") (pin "1") (pinfunction "1_1") (pintype "passive"))
      (node (ref "D3") (pin "2") (pinfunction "A_2") (pintype "bidirectional"))
      (node (ref "D4") (pin "1") (pinfunction "K_1") (pintype "bidirectional"))
    )
    (net (code "24") (name "Net-(D7-CATHODE)") (class "Default")
      (node (ref "D7") (pin "1") (pinfunction "CATHODE_1") (pintype "bidirectional"))
      (node (ref "R_CAPACITOR") (pin "1") (pinfunction "1_1") (pintype "passive"))
    )
    (net (code "25") (name "Net-(EPD_C1-Pad1)") (class "Default")
      (node (ref "EPD_C1") (pin "1") (pinfunction "1_1") (pintype "passive"))
      (node (ref "J1") (pin "4") (pinfunction "4_4") (pintype "bidirectional"))
    )
    (net (code "26") (name "Net-(EPD_C2-Pad1)") (class "Default")
      (node (ref "EPD_C2") (pin "1") (pinfunction "1_1") (pintype "passive"))
      (node (ref "J1") (pin "5") (pinfunction "5_5") (pintype "bidirectional"))
    )
    (net (code "27") (name "Net-(EPD_C6-Pad1)") (class "Default")
      (node (ref "EPD_C6") (pin "1") (pinfunction "1_1") (pintype "passive"))
      (node (ref "J1") (pin "18") (pinfunction "18_18") (pintype "bidirectional"))
    )
    (net (code "28") (name "Net-(EPD_C7-Pad1)") (class "Default")
      (node (ref "EPD_C7") (pin "1") (pinfunction "1_1") (pintype "passive"))
      (node (ref "J1") (pin "19") (pinfunction "19_19") (pintype "bidirectional"))
    )
    (net (code "29") (name "Net-(EPD_C8-Pad1)") (class "Default")
      (node (ref "EPD_C8") (pin "1") (pinfunction "1_1") (pintype "passive"))
      (node (ref "J1") (pin "20") (pinfunction "20_20") (pintype "bidirectional"))
    )
    (net (code "30") (name "Net-(EPD_C10-Pad1)") (class "Default")
      (node (ref "EPD_C10") (pin "1") (pinfunction "1_1") (pintype "passive"))
      (node (ref "J1") (pin "22") (pinfunction "22_22") (pintype "bidirectional"))
    )
    (net (code "31") (name "Net-(EPD_C12-Pad1)") (class "Default")
      (node (ref "EPD_C12") (pin "1") (pinfunction "1_1") (pintype "passive"))
      (node (ref "J1") (pin "24") (pinfunction "24_24") (pintype "bidirectional"))
    )
    (net (code "32") (name "Net-(IC1-CT)") (class "Default")
      (node (ref "C_DELAY") (pin "1") (pinfunction "1_1") (pintype "passive"))
      (node (ref "IC1") (pin "5") (pinfunction "CT_5") (pintype "bidirectional"))
    )
    (net (code "33") (name "Net-(J2-PadA5)") (class "Default")
      (node (ref "J2") (pin "A5") (pinfunction "A5_A5") (pintype "bidirectional"))
      (node (ref "R2-USB1") (pin "2") (pinfunction "2_2") (pintype "passive"))
    )
    (net (code "34") (name "Net-(J2-PadB5)") (class "Default")
      (node (ref "J2") (pin "B5") (pinfunction "B5_B5") (pintype "bidirectional"))
      (node (ref "R2-USB") (pin "1") (pinfunction "1_1") (pintype "passive"))
    )
    (net (code "35") (name "Net-(MCP73831-PROG)") (class "Default")
      (node (ref "MCP73831") (pin "5") (pinfunction "PROG_5") (pintype "input"))
      (node (ref "R2_BAT") (pin "2") (pinfunction "2_2") (pintype "passive"))
    )
    (net (code "36") (name "Net-(MCP73831-STAT)") (class "Default")
      (node (ref "MCP73831") (pin "1") (pinfunction "STAT_1") (pintype "output"))
      (node (ref "R1_BAT") (pin "1") (pinfunction "1_1") (pintype "passive"))
    )
    (net (code "37") (name "PREVGH") (class "Default")
      (node (ref "D5") (pin "1") (pinfunction "K_1") (pintype "bidirectional"))
      (node (ref "EPD_C9") (pin "1") (pinfunction "1_1") (pintype "passive"))
      (node (ref "J1") (pin "21") (pinfunction "21_21") (pintype "bidirectional"))
    )
    (net (code "38") (name "PREVGL") (class "Default")
      (node (ref "D4") (pin "2") (pinfunction "A_2") (pintype "bidirectional"))
      (node (ref "EPD_C11") (pin "1") (pinfunction "1_1") (pintype "passive"))
      (node (ref "J1") (pin "23") (pinfunction "23_23") (pintype "bidirectional"))
    )
    (net (code "39") (name "RESE") (class "Default")
      (node (ref "J1") (pin "3") (pinfunction "3_3") (pintype "bidirectional"))
      (node (ref "Q3") (pin "2") (pinfunction "S_2") (pintype "bidirectional"))
      (node (ref "R3") (pin "1") (pinfunction "1_1") (pintype "passive"))
    )
    (net (code "40") (name "RESE'") (class "Default")
      (node (ref "R2") (pin "2") (pinfunction "2_2") (pintype "passive"))
      (node (ref "R3") (pin "2") (pinfunction "2_2") (pintype "passive"))
      (node (ref "SJ1") (pin "2") (pinfunction "2_2") (pintype "passive"))
    )
    (net (code "41") (name "RESET") (class "Default")
      (node (ref "C5") (pin "1") (pinfunction "1_1") (pintype "passive"))
      (node (ref "IC1") (pin "1") (pinfunction "VOUT_1") (pintype "bidirectional"))
      (node (ref "RESET_BUTTON") (pin "3") (pinfunction "3_3") (pintype "passive"))
      (node (ref "RESET_BUTTON") (pin "4") (pinfunction "4_4") (pintype "passive"))
      (node (ref "R_RESET") (pin "2") (pinfunction "2_2") (pintype "passive"))
      (node (ref "U2") (pin "3") (pinfunction "EN_3") (pintype "input"))
    )
    (net (code "42") (name "RTC_RST") (class "Default")
      (node (ref "U2") (pin "16") (pinfunction "IO18_16") (pintype "bidirectional"))
      (node (ref "U3") (pin "4") (pinfunction "~{RST}_4") (pintype "input"))
    )
    (net (code "43") (name "RX") (class "Default")
      (node (ref "TP2") (pin "TP") (pinfunction "TP_TP") (pintype "input"))
      (node (ref "U2") (pin "24") (pinfunction "RXD0/GPIO17_24") (pintype "bidirectional"))
    )
    (net (code "44") (name "SCK") (class "Default")
      (node (ref "D10") (pin "1") (pinfunction "1_1") (pintype "passive"))
      (node (ref "J1") (pin "13") (pinfunction "13_13") (pintype "bidirectional"))
      (node (ref "J4") (pin "P5") (pinfunction "CLK_P5") (pintype "bidirectional"))
      (node (ref "R6") (pin "1") (pinfunction "1_1") (pintype "passive"))
      (node (ref "TP8") (pin "TP") (pinfunction "TP_TP") (pintype "input"))
      (node (ref "U1") (pin "6") (pinfunction "CLK_6") (pintype "input"))
      (node (ref "U2") (pin "6") (pinfunction "IO6_6") (pintype "bidirectional"))
    )
    (net (code "45") (name "SCL") (class "Default")
      (node (ref "J3") (pin "4") (pinfunction "4_4") (pintype "passive"))
      (node (ref "R2-PINH") (pin "1") (pinfunction "1_1") (pintype "passive"))
      (node (ref "SENSOR2") (pin "4") (pinfunction "SCK_4") (pintype "input"))
      (node (ref "U2") (pin "20") (pinfunction "IO22_20") (pintype "bidirectional"))
      (node (ref "U3") (pin "16") (pinfunction "SCL_16") (pintype "input"))
      (node (ref "U4") (pin "7") (pinfunction "SCL_7") (pintype "input"))
    )
    (net (code "46") (name "SDA") (class "Default")
      (node (ref "J3") (pin "3") (pinfunction "3_3") (pintype "passive"))
      (node (ref "R1_PINH") (pin "1") (pinfunction "1_1") (pintype "passive"))
      (node (ref "SENSOR2") (pin "3") (pinfunction "SDI_3") (pintype "bidirectional"))
      (node (ref "U2") (pin "19") (pinfunction "IO21_19") (pintype "bidirectional"))
      (node (ref "U3") (pin "15") (pinfunction "SDA_15") (pintype "bidirectional"))
      (node (ref "U4") (pin "8") (pinfunction "SDA_8") (pintype "bidirectional"))
    )
    (net (code "47") (name "SRC") (class "Default")
      (node (ref "C4") (pin "2") (pinfunction "2_2") (pintype "passive"))
      (node (ref "D5") (pin "2") (pinfunction "A_2") (pintype "bidirectional"))
      (node (ref "L1") (pin "1") (pinfunction "1_1") (pintype "passive"))
      (node (ref "Q3") (pin "3") (pinfunction "D_3") (pintype "bidirectional"))
    )
    (net (code "48") (name "SS_SD") (class "Default")
      (node (ref "D8") (pin "1") (pinfunction "1_1") (pintype "passive"))
      (node (ref "J4") (pin "P2") (pinfunction "CD/DAT3_P2") (pintype "bidirectional"))
      (node (ref "R10") (pin "1") (pinfunction "1_1") (pintype "passive"))
      (node (ref "U2") (pin "4") (pinfunction "IO4_4") (pintype "bidirectional"))
    )
    (net (code "49") (name "TX") (class "Default")
      (node (ref "TP1") (pin "TP") (pinfunction "TP_TP") (pintype "input"))
      (node (ref "U2") (pin "25") (pinfunction "TXD0/GPIO16_25") (pintype "bidirectional"))
    )
    (net (code "50") (name "USB_D+") (class "Default")
      (node (ref "D1") (pin "1") (pinfunction "I/O1_1_1") (pintype "bidirectional"))
      (node (ref "U2") (pin "14") (pinfunction "IO13_14") (pintype "bidirectional"))
    )
    (net (code "51") (name "USB_D-") (class "Default")
      (node (ref "D1") (pin "3") (pinfunction "I/O2_1_3") (pintype "bidirectional"))
      (node (ref "U2") (pin "13") (pinfunction "IO12_13") (pintype "bidirectional"))
    )
    (net (code "52") (name "VBAT") (class "Default")
      (node (ref "C2_BAT") (pin "1") (pinfunction "1_1") (pintype "passive"))
      (node (ref "MCP73831") (pin "3") (pinfunction "VBAT_3") (pintype "power_in"))
      (node (ref "Q1") (pin "3") (pinfunction "D_3") (pintype "bidirectional"))
      (node (ref "TP3") (pin "TP") (pinfunction "TP_TP") (pintype "input"))
      (node (ref "U4") (pin "2") (pinfunction "CELL_2") (pintype "power_in"))
      (node (ref "U4") (pin "3") (pinfunction "VDD_3") (pintype "power_in"))
    )
    (net (code "53") (name "VBUS") (class "Default")
      (node (ref "C1_BAT") (pin "1") (pinfunction "1_1") (pintype "passive"))
      (node (ref "C4_USB") (pin "1") (pinfunction "1_1") (pintype "passive"))
      (node (ref "C5_USB") (pin "1") (pinfunction "1_1") (pintype "passive"))
      (node (ref "CHG_LED") (pin "A") (pinfunction "A_A") (pintype "passive"))
      (node (ref "D1") (pin "5") (pinfunction "VBUS_5") (pintype "bidirectional"))
      (node (ref "D2") (pin "2") (pinfunction "ANODE_2") (pintype "bidirectional"))
      (node (ref "MCP73831") (pin "4") (pinfunction "VIN_4") (pintype "power_in"))
      (node (ref "PFMF.050.1") (pin "2") (pinfunction "2_2") (pintype "passive"))
      (node (ref "Q1") (pin "1") (pinfunction "G_1") (pintype "bidirectional"))
      (node (ref "R1_PWRUSB") (pin "2") (pinfunction "2_2") (pintype "passive"))
      (node (ref "TP14") (pin "TP") (pinfunction "TP_TP") (pintype "input"))
    )
    (net (code "54") (name "VRTC") (class "Default")
      (node (ref "C10_SUPERCAP") (pin "2") (pinfunction "2_2") (pintype "passive"))
      (node (ref "C8") (pin "1") (pinfunction "1_1") (pintype "passive"))
      (node (ref "R_CAPACITOR") (pin "2") (pinfunction "2_2") (pintype "passive"))
      (node (ref "U3") (pin "14") (pinfunction "VBAT_14") (pintype "power_in"))
    )
    (net (code "55") (name "VUSB") (class "Default")
      (node (ref "J2") (pin "A4") (pinfunction "A4_A4") (pintype "bidirectional"))
      (node (ref "J2") (pin "A9") (pinfunction "A9_A9") (pintype "bidirectional"))
      (node (ref "J2") (pin "B4") (pinfunction "B4_B4") (pintype "bidirectional"))
      (node (ref "J2") (pin "B9") (pinfunction "B9_B9") (pintype "bidirectional"))
      (node (ref "PFMF.050.1") (pin "1") (pinfunction "1_1") (pintype "passive"))
    )
    (net (code "56") (name "unconnected-(IC1-NC-Pad4)") (class "Default")
      (node (ref "IC1") (pin "4") (pinfunction "NC_4") (pintype "no_connect"))
    )
    (net (code "57") (name "unconnected-(IC4-NC-Pad4)") (class "Default")
      (node (ref "IC4") (pin "4") (pinfunction "NC_4") (pintype "no_connect"))
    )
    (net (code "58") (name "unconnected-(J1-Pad1)") (class "Default")
      (node (ref "J1") (pin "1") (pinfunction "1_1") (pintype "bidirectional"))
    )
    (net (code "59") (name "unconnected-(J1-Pad6)") (class "Default")
      (node (ref "J1") (pin "6") (pinfunction "6_6") (pintype "bidirectional"))
    )
    (net (code "60") (name "unconnected-(J1-Pad7)") (class "Default")
      (node (ref "J1") (pin "7") (pinfunction "7_7") (pintype "bidirectional"))
    )
    (net (code "61") (name "unconnected-(J2-PadA8)") (class "Default")
      (node (ref "J2") (pin "A8") (pinfunction "A8_A8") (pintype "bidirectional"))
    )
    (net (code "62") (name "unconnected-(J2-PadB8)") (class "Default")
      (node (ref "J2") (pin "B8") (pinfunction "B8_B8") (pintype "bidirectional"))
    )
    (net (code "63") (name "unconnected-(J4-DAT1-PadP8)") (class "Default")
      (node (ref "J4") (pin "P8") (pinfunction "DAT1_P8") (pintype "bidirectional"))
    )
    (net (code "64") (name "unconnected-(J4-DAT2-PadP1)") (class "Default")
      (node (ref "J4") (pin "P1") (pinfunction "DAT2_P1") (pintype "bidirectional"))
    )
    (net (code "65") (name "unconnected-(J4-DETECTION_1-PadS1)") (class "Default")
      (node (ref "J4") (pin "S1") (pinfunction "DETECTION_1_S1") (pintype "bidirectional"))
    )
    (net (code "66") (name "unconnected-(J4-DETECTION_2-PadS2)") (class "Default")
      (node (ref "J4") (pin "S2") (pinfunction "DETECTION_2_S2") (pintype "bidirectional"))
    )
    (net (code "67") (name "unconnected-(U2-NC-Pad22)") (class "Default")
      (node (ref "U2") (pin "22") (pinfunction "NC_22") (pintype "no_connect"))
    )
    (net (code "68") (name "unconnected-(U4-~{ALERT}-Pad5)") (class "Default")
      (node (ref "U4") (pin "5") (pinfunction "~{ALERT}_5") (pintype "output"))
    )
  )
)
